# i2c.net
KiCad netlist of a schematic drawn in EAGLE
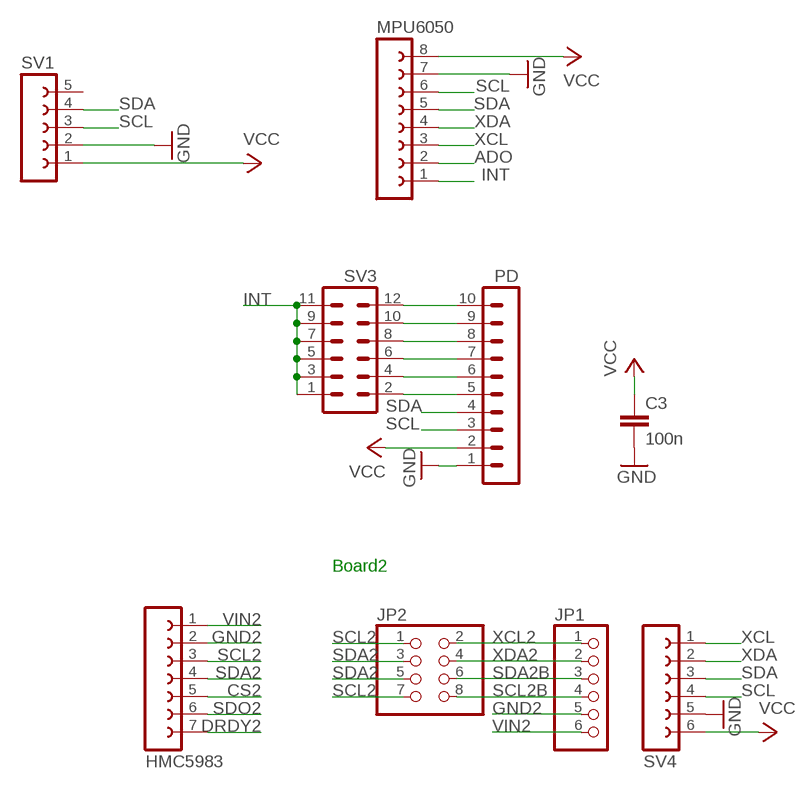
[diagram p0: schematic, sheet 1]

(export (version "E")
  (design (tool "Eeschema 10.0.6"))
  (components
    (comp (ref "C3")
      (value "100n")
      (footprint "eagle-import:C025-024X044")
      (libsource (lib "eagle-import") (part "C-EU025-024X044"))
    )
    (comp (ref "HMC5983")
      (value "FE07-1")
      (footprint "eagle-import:FE07")
      (libsource (lib "eagle-import") (part "FE07-1"))
    )
    (comp (ref "JP1")
      (value "PINHD-1X6/90")
      (footprint "eagle-import:1X06_90")
      (libsource (lib "eagle-import") (part "PINHD-1X6/90"))
    )
    (comp (ref "JP2")
      (value "PINHD-2X4")
      (footprint "eagle-import:2X04")
      (libsource (lib "eagle-import") (part "PINHD-2X4"))
    )
    (comp (ref "MPU6050")
      (value "FE08W")
      (footprint "eagle-import:FE08W")
      (libsource (lib "eagle-import") (part "FE08W"))
    )
    (comp (ref "PD")
      (value "MA10-1W")
      (footprint "eagle-import:MA10-1W")
      (libsource (lib "eagle-import") (part "MA10-1W"))
    )
    (comp (ref "SV1")
      (value "FE05-1")
      (footprint "eagle-import:FE05-1")
      (libsource (lib "eagle-import") (part "FE05-1"))
    )
    (comp (ref "SV3")
      (value "MA06-2")
      (footprint "eagle-import:MA06-2")
      (libsource (lib "eagle-import") (part "MA06-2"))
    )
    (comp (ref "SV4")
      (value "FE06-1")
      (footprint "eagle-import:FE06")
      (libsource (lib "eagle-import") (part "FE06-1"))
    )
  )
  (nets
    (net (code "1") (name "/ADO") (class "Default")
      (node (ref "MPU6050") (pin "2") (pinfunction "2_2") (pintype "passive"))
    )
    (net (code "2") (name "/CS2") (class "Default")
      (node (ref "HMC5983") (pin "5") (pinfunction "5_5") (pintype "passive"))
    )
    (net (code "3") (name "/DRDY2") (class "Default")
      (node (ref "HMC5983") (pin "7") (pinfunction "7_7") (pintype "passive"))
    )
    (net (code "4") (name "/GND2") (class "Default")
      (node (ref "HMC5983") (pin "2") (pinfunction "2_2") (pintype "passive"))
      (node (ref "JP1") (pin "5") (pinfunction "5_5") (pintype "passive"))
    )
    (net (code "5") (name "/INT") (class "Default")
      (node (ref "MPU6050") (pin "1") (pinfunction "1_1") (pintype "passive"))
      (node (ref "SV3") (pin "1") (pinfunction "1_1") (pintype "passive"))
      (node (ref "SV3") (pin "11") (pinfunction "11_11") (pintype "passive"))
      (node (ref "SV3") (pin "3") (pinfunction "3_3") (pintype "passive"))
      (node (ref "SV3") (pin "5") (pinfunction "5_5") (pintype "passive"))
      (node (ref "SV3") (pin "7") (pinfunction "7_7") (pintype "passive"))
      (node (ref "SV3") (pin "9") (pinfunction "9_9") (pintype "passive"))
    )
    (net (code "6") (name "/SCL") (class "Default")
      (node (ref "MPU6050") (pin "6") (pinfunction "6_6") (pintype "passive"))
      (node (ref "PD") (pin "3") (pinfunction "3_3") (pintype "passive"))
      (node (ref "SV1") (pin "3") (pinfunction "3_3") (pintype "passive"))
      (node (ref "SV4") (pin "4") (pinfunction "4_4") (pintype "passive"))
    )
    (net (code "7") (name "/SCL2") (class "Default")
      (node (ref "HMC5983") (pin "3") (pinfunction "3_3") (pintype "passive"))
      (node (ref "JP2") (pin "1") (pinfunction "1_1") (pintype "passive"))
      (node (ref "JP2") (pin "7") (pinfunction "7_7") (pintype "passive"))
    )
    (net (code "8") (name "/SCL2B") (class "Default")
      (node (ref "JP1") (pin "4") (pinfunction "4_4") (pintype "passive"))
      (node (ref "JP2") (pin "8") (pinfunction "8_8") (pintype "passive"))
    )
    (net (code "9") (name "/SDA") (class "Default")
      (node (ref "MPU6050") (pin "5") (pinfunction "5_5") (pintype "passive"))
      (node (ref "PD") (pin "4") (pinfunction "4_4") (pintype "passive"))
      (node (ref "SV1") (pin "4") (pinfunction "4_4") (pintype "passive"))
      (node (ref "SV4") (pin "3") (pinfunction "3_3") (pintype "passive"))
    )
    (net (code "10") (name "/SDA2") (class "Default")
      (node (ref "HMC5983") (pin "4") (pinfunction "4_4") (pintype "passive"))
      (node (ref "JP2") (pin "3") (pinfunction "3_3") (pintype "passive"))
      (node (ref "JP2") (pin "5") (pinfunction "5_5") (pintype "passive"))
    )
    (net (code "11") (name "/SDA2B") (class "Default")
      (node (ref "JP1") (pin "3") (pinfunction "3_3") (pintype "passive"))
      (node (ref "JP2") (pin "6") (pinfunction "6_6") (pintype "passive"))
    )
    (net (code "12") (name "/SDO2") (class "Default")
      (node (ref "HMC5983") (pin "6") (pinfunction "6_6") (pintype "passive"))
    )
    (net (code "13") (name "/VIN2") (class "Default")
      (node (ref "HMC5983") (pin "1") (pinfunction "1_1") (pintype "passive"))
      (node (ref "JP1") (pin "6") (pinfunction "6_6") (pintype "passive"))
    )
    (net (code "14") (name "/XCL") (class "Default")
      (node (ref "MPU6050") (pin "3") (pinfunction "3_3") (pintype "passive"))
      (node (ref "SV4") (pin "1") (pinfunction "1_1") (pintype "passive"))
    )
    (net (code "15") (name "/XCL2") (class "Default")
      (node (ref "JP1") (pin "1") (pinfunction "1_1") (pintype "passive"))
      (node (ref "JP2") (pin "2") (pinfunction "2_2") (pintype "passive"))
    )
    (net (code "16") (name "/XDA") (class "Default")
      (node (ref "MPU6050") (pin "4") (pinfunction "4_4") (pintype "passive"))
      (node (ref "SV4") (pin "2") (pinfunction "2_2") (pintype "passive"))
    )
    (net (code "17") (name "/XDA2") (class "Default")
      (node (ref "JP1") (pin "2") (pinfunction "2_2") (pintype "passive"))
      (node (ref "JP2") (pin "4") (pinfunction "4_4") (pintype "passive"))
    )
    (net (code "18") (name "GND") (class "Default")
      (node (ref "C3") (pin "2") (pinfunction "2_2") (pintype "passive"))
      (node (ref "MPU6050") (pin "7") (pinfunction "7_7") (pintype "passive"))
      (node (ref "PD") (pin "1") (pinfunction "1_1") (pintype "passive"))
      (node (ref "SV1") (pin "2") (pinfunction "2_2") (pintype "passive"))
      (node (ref "SV4") (pin "5") (pinfunction "5_5") (pintype "passive"))
    )
    (net (code "19") (name "Net-(PD-Pad5)") (class "Default")
      (node (ref "PD") (pin "5") (pinfunction "5_5") (pintype "passive"))
      (node (ref "SV3") (pin "2") (pinfunction "2_2") (pintype "passive"))
    )
    (net (code "20") (name "Net-(PD-Pad6)") (class "Default")
      (node (ref "PD") (pin "6") (pinfunction "6_6") (pintype "passive"))
      (node (ref "SV3") (pin "4") (pinfunction "4_4") (pintype "passive"))
    )
    (net (code "21") (name "Net-(PD-Pad7)") (class "Default")
      (node (ref "PD") (pin "7") (pinfunction "7_7") (pintype "passive"))
      (node (ref "SV3") (pin "6") (pinfunction "6_6") (pintype "passive"))
    )
    (net (code "22") (name "Net-(PD-Pad8)") (class "Default")
      (node (ref "PD") (pin "8") (pinfunction "8_8") (pintype "passive"))
      (node (ref "SV3") (pin "8") (pinfunction "8_8") (pintype "passive"))
    )
    (net (code "23") (name "Net-(PD-Pad9)") (class "Default")
      (node (ref "PD") (pin "9") (pinfunction "9_9") (pintype "passive"))
      (node (ref "SV3") (pin "10") (pinfunction "10_10") (pintype "passive"))
    )
    (net (code "24") (name "Net-(PD-Pad10)") (class "Default")
      (node (ref "PD") (pin "10") (pinfunction "10_10") (pintype "passive"))
      (node (ref "SV3") (pin "12") (pinfunction "12_12") (pintype "passive"))
    )
    (net (code "25") (name "VCC") (class "Default")
      (node (ref "C3") (pin "1") (pinfunction "1_1") (pintype "passive"))
      (node (ref "MPU6050") (pin "8") (pinfunction "8_8") (pintype "passive"))
      (node (ref "PD") (pin "2") (pinfunction "2_2") (pintype "passive"))
      (node (ref "SV1") (pin "1") (pinfunction "1_1") (pintype "passive"))
      (node (ref "SV4") (pin "6") (pinfunction "6_6") (pintype "passive"))
    )
    (net (code "26") (name "unconnected-(SV1-Pad5)") (class "Default")
      (node (ref "SV1") (pin "5") (pinfunction "5_5") (pintype "passive"))
    )
  )
)
